# light_brick.net
KiCad netlist of a schematic drawn in EAGLE
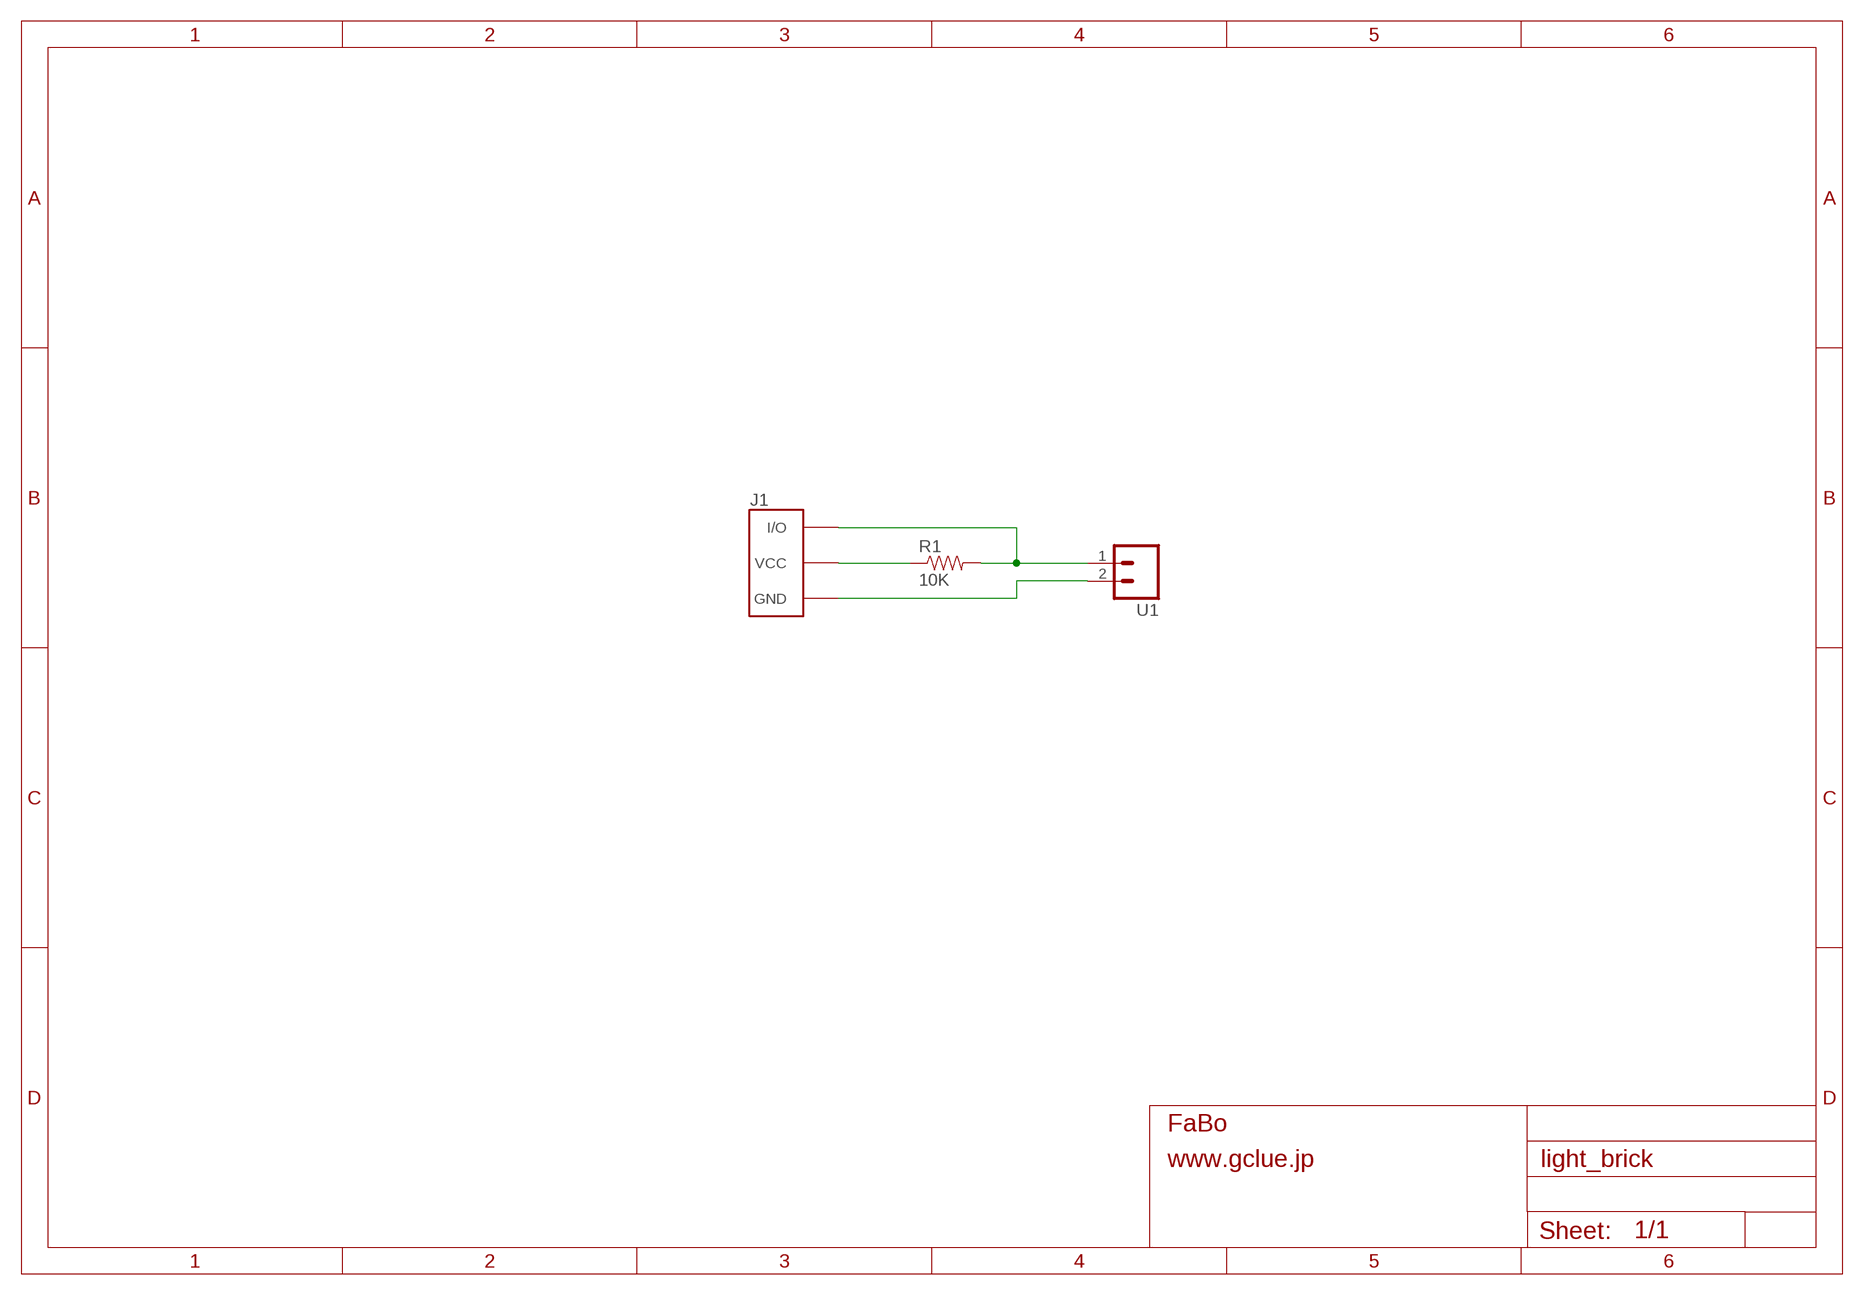
[diagram p0: schematic, sheet 1]

(export (version "E")
  (design (tool "Eeschema 10.0.6"))
  (components
    (comp (ref "J1")
      (value "BRICK_3PIN")
      (footprint "eagle-import:BRICK_3PIN")
      (libsource (lib "eagle-import") (part "BRICK_3PIN"))
    )
    (comp (ref "R1")
      (value "10K")
      (footprint "eagle-import:AXIAL-0.3")
      (libsource (lib "eagle-import") (part "RESISTORAXIAL-0.3"))
    )
    (comp (ref "U1")
      (value "M02NG")
      (footprint "eagle-import:1X02")
      (libsource (lib "eagle-import") (part "M02NG"))
    )
  )
  (nets
    (net (code "1") (name "Net-(J1-I{slash}O)") (class "Default")
      (node (ref "J1") (pin "IN/OUT") (pinfunction "I/O_IN/OUT") (pintype "bidirectional"))
      (node (ref "R1") (pin "P$2") (pinfunction "2_P$2") (pintype "passive"))
      (node (ref "U1") (pin "1") (pinfunction "1_1") (pintype "passive"))
    )
    (net (code "2") (name "Net-(J1-PadGND)") (class "Default")
      (node (ref "J1") (pin "GND") (pinfunction "GND_GND") (pintype "bidirectional"))
      (node (ref "U1") (pin "2") (pinfunction "2_2") (pintype "passive"))
    )
    (net (code "3") (name "Net-(R1-1)") (class "Default")
      (node (ref "J1") (pin "VCC") (pinfunction "VCC_VCC") (pintype "bidirectional"))
      (node (ref "R1") (pin "P$1") (pinfunction "1_P$1") (pintype "passive"))
    )
  )
)
